# CAN_Interface.net
KiCad netlist of a schematic drawn in Altium Designer
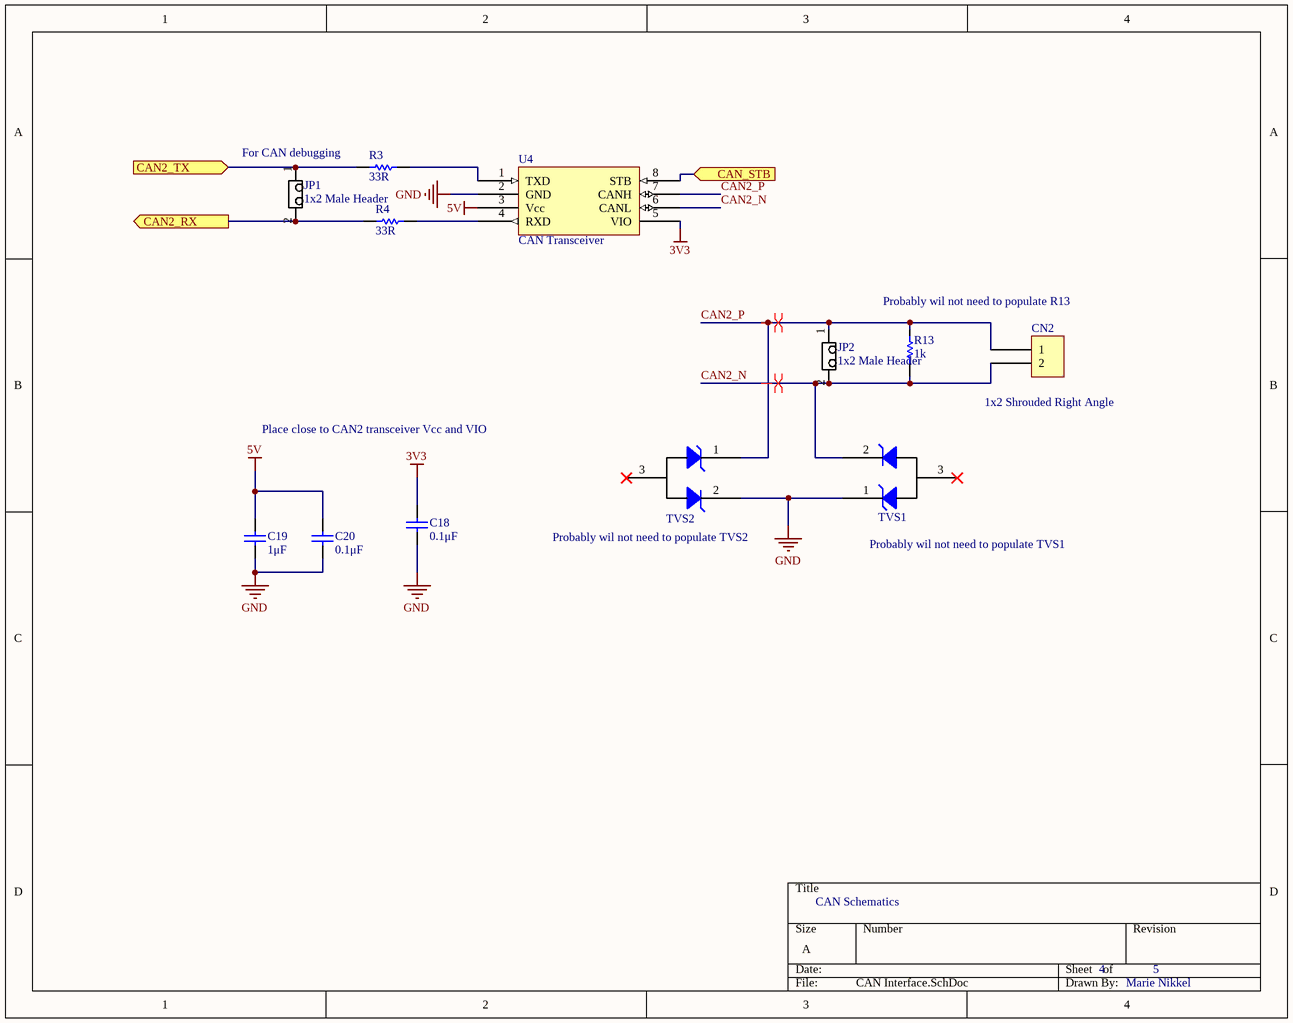
[diagram p0: CAN Interface.SchDoc]

(export (version "E")
  (design (tool "Eeschema 10.0.6"))
  (components
    (comp (ref "C18")
      (value "0.1μF")
      (footprint "CAPC1608N(0603\")")
      (description "Capacitor, Ceramic, 16V, +/- 10%, 0603 SMD, X7R")
      (fields (field (name "PUBLISHER") "AUVic") (field (name "CREATED BY") "Andy Bates"))
      (libsource (lib "AUVic_Integrated_Library_Capacitors") (part "0.1uF 16V 0603 SMD, Ceramic"))
    )
    (comp (ref "C19")
      (value "1μF")
      (footprint "CAPC1608N(0603\")")
      (description "Capacitor, Ceramic, 50V, +/- 10%, 0603 SMD, X5R")
      (fields (field (name "CREATED BY") "Lyden Smith"))
      (libsource (lib "AUVic_Integrated_Library_Capacitors") (part "1uF 50V 0603 SMD, Ceramic"))
    )
    (comp (ref "C20")
      (value "0.1μF")
      (footprint "CAPC1608N(0603\")")
      (description "Capacitor, Ceramic, 16V, +/- 10%, 0603 SMD, X7R")
      (fields (field (name "PUBLISHER") "AUVic") (field (name "CREATED BY") "Andy Bates"))
      (libsource (lib "AUVic_Integrated_Library_Capacitors") (part "0.1uF 16V 0603 SMD, Ceramic"))
    )
    (comp (ref "CN2")
      (value "1x2 Shrouded Right Angle")
      (footprint "2X1 Female Header")
      (description "02 MTE HDR SRRA LATCH")
      (libsource (lib "AUVIC") (part "1x2 Shrouded Right Angle"))
    )
    (comp (ref "JP1")
      (value "1x2 Male Header")
      (footprint "2X1 Males Header")
      (fields (field (name "MADE BY") "Andy Bates"))
      (libsource (lib "AUVIC") (part "1x2 Male Header"))
    )
    (comp (ref "JP2")
      (value "1x2 Male Header")
      (footprint "2X1 Males Header")
      (fields (field (name "MADE BY") "Andy Bates"))
      (libsource (lib "AUVIC") (part "1x2 Male Header"))
    )
    (comp (ref "R3")
      (value "RC0603FR-0733RL")
      (footprint "RESC1608X55X25NL10T15")
      (description "Res Thick Film 0603 33 Ohm 1% 1/10W +/-100ppm/ßC Molded SMD Paper T/R")
      (fields (field (name "RESISTANCE") "33R") (field (name "TOLERANCE") "1%"))
      (libsource (lib "AUVIC") (part "RES-2"))
    )
    (comp (ref "R4")
      (value "RC0603FR-0733RL")
      (footprint "RESC1608X55X25NL10T15")
      (description "Res Thick Film 0603 33 Ohm 1% 1/10W +/-100ppm/ßC Molded SMD Paper T/R")
      (fields (field (name "RESISTANCE") "33R") (field (name "TOLERANCE") "1%"))
      (libsource (lib "AUVIC") (part "RES-2"))
    )
    (comp (ref "R13")
      (value "1k")
      (footprint "RESC1608N(0603\")")
      (description "1kR, 1%, 1/10W , 0603, SMD")
      (fields (field (name "CREATED BY") "Andy Bates") (field (name "PUBLISHER") "AUVic"))
      (libsource (lib "AUVic_Integrated_Library_Resistors") (part "1kR, 1%, 1/10W , 0603, SMD"))
    )
    (comp (ref "TVS1")
      (value "PESD36VS2UT,215")
      (footprint "SOT95P245X110-3N")
      (description "TVS DIODE 36V 60V SOT23")
      (fields (field (name "CREATED BY") "Miguel Manguerra"))
      (libsource (lib "AUVic_Integrated_Library_Diodes") (part "PESD36VS2UT,215"))
    )
    (comp (ref "TVS2")
      (value "PESD36VS2UT,215")
      (footprint "SOT95P245X110-3N")
      (description "TVS DIODE 36V 60V SOT23")
      (fields (field (name "CREATED BY") "Miguel Manguerra"))
      (libsource (lib "AUVic_Integrated_Library_Diodes") (part "PESD36VS2UT,215"))
    )
    (comp (ref "U4")
      (value "CAN Transceiver")
      (footprint "8-SOIC")
      (description "1/1 Transceiver Half CANbus 8-SO")
      (libsource (lib "AUVIC") (part "CAN Transceiver"))
    )
  )
  (nets
    (net (code "1") (name "/CAN2_N") (class "Default")
      (node (ref "CN2") (pin "2") (pinfunction "2_2") (pintype "passive"))
      (node (ref "JP2") (pin "2") (pinfunction "2_2") (pintype "passive"))
      (node (ref "R13") (pin "1") (pinfunction "1_1") (pintype "passive"))
      (node (ref "TVS1") (pin "2") (pinfunction "Cathode_2_2") (pintype "passive"))
      (node (ref "U4") (pin "6") (pinfunction "CANL_6") (pintype "bidirectional"))
    )
    (net (code "2") (name "/CAN2_P") (class "Default")
      (node (ref "CN2") (pin "1") (pinfunction "1_1") (pintype "passive"))
      (node (ref "JP2") (pin "1") (pinfunction "1_1") (pintype "passive"))
      (node (ref "R13") (pin "2") (pinfunction "2_2") (pintype "passive"))
      (node (ref "TVS2") (pin "1") (pinfunction "Cathode_1_1") (pintype "passive"))
      (node (ref "U4") (pin "7") (pinfunction "CANH_7") (pintype "bidirectional"))
    )
    (net (code "3") (name "/CAN2_RX") (class "Default")
      (node (ref "JP1") (pin "2") (pinfunction "2_2") (pintype "passive"))
      (node (ref "R4") (pin "1") (pinfunction "1_1") (pintype "passive"))
    )
    (net (code "4") (name "/CAN2_TX") (class "Default")
      (node (ref "JP1") (pin "1") (pinfunction "1_1") (pintype "passive"))
      (node (ref "R3") (pin "1") (pinfunction "1_1") (pintype "passive"))
    )
    (net (code "5") (name "/CAN_STB") (class "Default")
      (node (ref "U4") (pin "8") (pinfunction "STB_8") (pintype "input"))
    )
    (net (code "6") (name "3V3") (class "Default")
      (node (ref "C18") (pin "2") (pinfunction "Cathode_2") (pintype "passive"))
      (node (ref "U4") (pin "5") (pinfunction "VIO_5") (pintype "passive"))
    )
    (net (code "7") (name "5V") (class "Default")
      (node (ref "C19") (pin "2") (pinfunction "Cathode_2") (pintype "passive"))
      (node (ref "C20") (pin "2") (pinfunction "Cathode_2") (pintype "passive"))
      (node (ref "U4") (pin "3") (pinfunction "Vcc_3") (pintype "power_in"))
    )
    (net (code "8") (name "GND") (class "Default")
      (node (ref "C18") (pin "1") (pinfunction "Anode_1") (pintype "passive"))
      (node (ref "C19") (pin "1") (pinfunction "Anode_1") (pintype "passive"))
      (node (ref "C20") (pin "1") (pinfunction "Anode_1") (pintype "passive"))
      (node (ref "TVS1") (pin "1") (pinfunction "Cathode_1_1") (pintype "passive"))
      (node (ref "TVS2") (pin "2") (pinfunction "Cathode_2_2") (pintype "passive"))
      (node (ref "U4") (pin "2") (pinfunction "GND_2") (pintype "power_in"))
    )
    (net (code "9") (name "Net-(U4-RXD)") (class "Default")
      (node (ref "R4") (pin "2") (pinfunction "2_2") (pintype "passive"))
      (node (ref "U4") (pin "4") (pinfunction "RXD_4") (pintype "output"))
    )
    (net (code "10") (name "Net-(U4-TXD)") (class "Default")
      (node (ref "R3") (pin "2") (pinfunction "2_2") (pintype "passive"))
      (node (ref "U4") (pin "1") (pinfunction "TXD_1") (pintype "input"))
    )
    (net (code "11") (name "unconnected-(TVS1-Common_Anode-Pad3)") (class "Default")
      (node (ref "TVS1") (pin "3") (pinfunction "Common_Anode_3") (pintype "passive"))
    )
    (net (code "12") (name "unconnected-(TVS2-Common_Anode-Pad3)") (class "Default")
      (node (ref "TVS2") (pin "3") (pinfunction "Common_Anode_3") (pintype "passive"))
    )
  )
)
